# IR_LED.net
KiCad netlist of a schematic drawn in Altium Designer
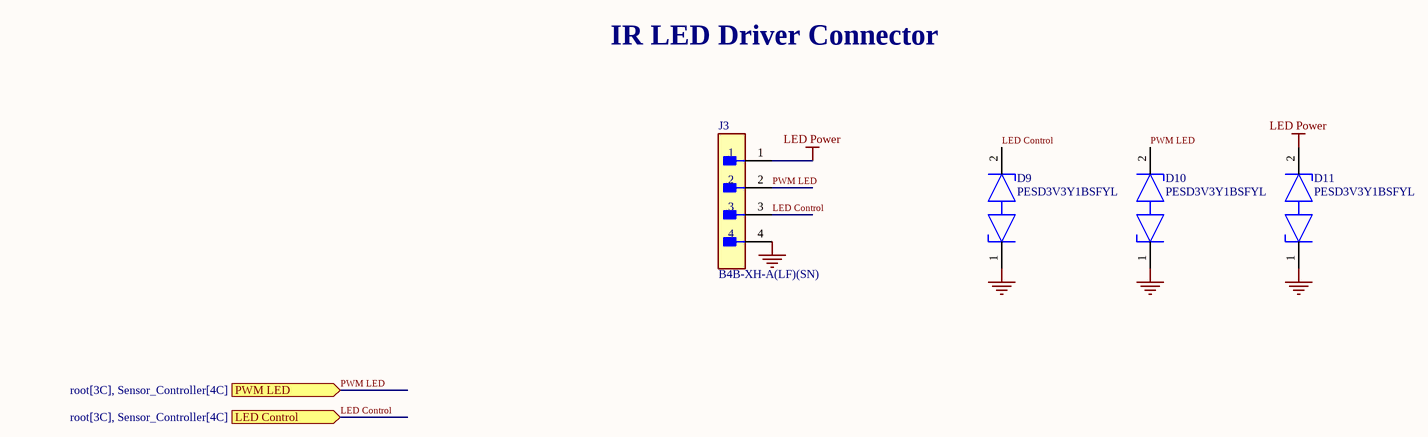
[diagram p0: IR_LED.SchDoc]

(export (version "E")
  (design (tool "Eeschema 10.0.6"))
  (components
    (comp (ref "D9")
      (value "PESD3V3Y1BSFYL")
      (footprint "FP-SOD962-2-CA-MFG")
      (description "PESD3V3Y1BSFYL PESD4V0Y1BSF - Extremely low capacitance bidirectional ESD protection diode")
      (libsource (lib "Altium Content Vault") (part "3f15ade4c48aeaca3578241bea7d4a4"))
    )
    (comp (ref "D10")
      (value "PESD3V3Y1BSFYL")
      (footprint "FP-SOD962-2-CA-MFG")
      (description "PESD3V3Y1BSFYL PESD4V0Y1BSF - Extremely low capacitance bidirectional ESD protection diode")
      (libsource (lib "Altium Content Vault") (part "3f15ade4c48aeaca3578241bea7d4a4"))
    )
    (comp (ref "D11")
      (value "PESD3V3Y1BSFYL")
      (footprint "FP-SOD962-2-CA-MFG")
      (description "PESD3V3Y1BSFYL PESD4V0Y1BSF - Extremely low capacitance bidirectional ESD protection diode")
      (libsource (lib "Altium Content Vault") (part "3f15ade4c48aeaca3578241bea7d4a4"))
    )
    (comp (ref "J3")
      (value "B4B-XH-A(LF)(SN)")
      (footprint "FP-B4B-XH-A_LF_SN-MFG")
      (description "CONN HEADER VERT 4POS 2.5MM")
      (libsource (lib "Altium Content Vault") (part "299a8cea1bdcbc3624fe62c390fa72c"))
    )
  )
  (nets
    (net (code "1") (name "/LED Control") (class "Default")
      (node (ref "D9") (pin "2") (pinfunction "2_2") (pintype "passive"))
      (node (ref "J3") (pin "3") (pinfunction "3_3") (pintype "passive"))
    )
    (net (code "2") (name "/PWM LED") (class "Default")
      (node (ref "D10") (pin "2") (pinfunction "2_2") (pintype "passive"))
      (node (ref "J3") (pin "2") (pinfunction "2_2") (pintype "passive"))
    )
    (net (code "3") (name "GND") (class "Default")
      (node (ref "D10") (pin "1") (pinfunction "1_1") (pintype "passive"))
      (node (ref "D11") (pin "1") (pinfunction "1_1") (pintype "passive"))
      (node (ref "D9") (pin "1") (pinfunction "1_1") (pintype "passive"))
      (node (ref "J3") (pin "4") (pinfunction "4_4") (pintype "passive"))
    )
    (net (code "4") (name "LED Power") (class "Default")
      (node (ref "D11") (pin "2") (pinfunction "2_2") (pintype "passive"))
      (node (ref "J3") (pin "1") (pinfunction "1_1") (pintype "passive"))
    )
  )
)
